# espnative-deadrail-2-2.net
KiCad netlist of a schematic drawn in EAGLE
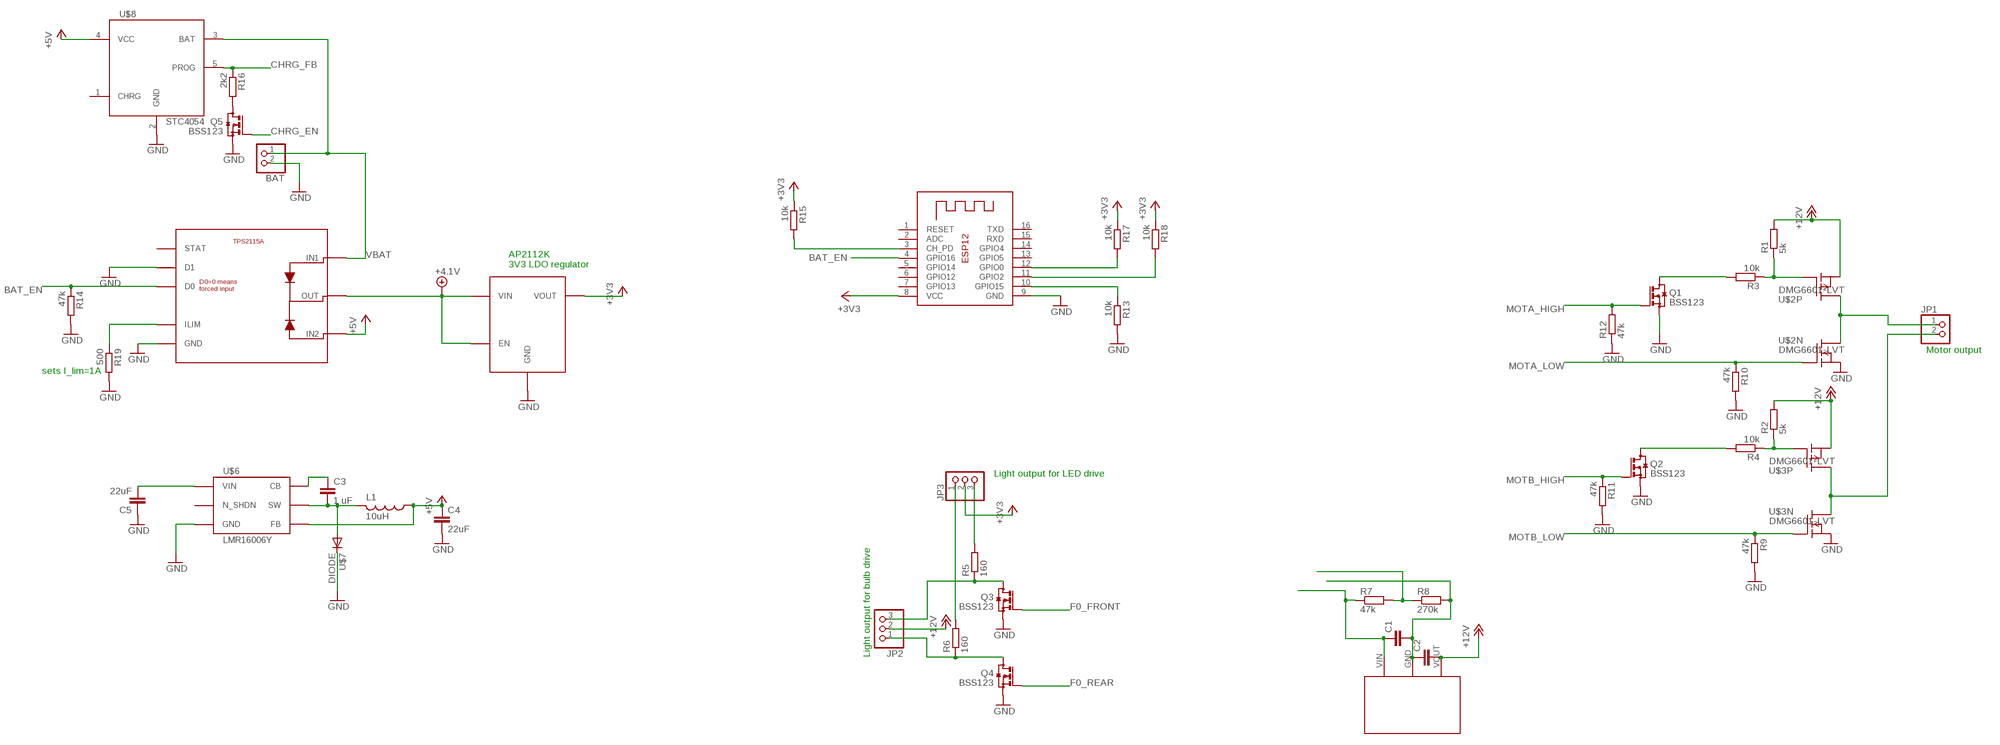
[diagram p0: schematic, sheet 1]

(export (version "E")
  (design (tool "Eeschema 10.0.6"))
  (components
    (comp (ref "BAT")
      (value "JST_2PIN-SMT-RA")
      (footprint "eagle-import:JST-PH-2-SMT-RA")
      (libsource (lib "eagle-import") (part "JST_2PIN-SMT-RA"))
    )
    (comp (ref "C1")
      (value "C-EUC1210")
      (footprint "eagle-import:C1210")
      (libsource (lib "eagle-import") (part "C-EUC1210"))
    )
    (comp (ref "C2")
      (value "C-EUC1210")
      (footprint "eagle-import:C1210")
      (libsource (lib "eagle-import") (part "C-EUC1210"))
    )
    (comp (ref "C3")
      (value "1 uF")
      (footprint "eagle-import:C0603")
      (libsource (lib "eagle-import") (part "C-EUC0603"))
    )
    (comp (ref "C4")
      (value "22uF")
      (footprint "eagle-import:C0603")
      (libsource (lib "eagle-import") (part "C-EUC0603"))
    )
    (comp (ref "C5")
      (value "22uF")
      (footprint "eagle-import:C1206")
      (libsource (lib "eagle-import") (part "C-EUC1206"))
    )
    (comp (ref "JP1")
      (value "PINHD-1X2")
      (footprint "eagle-import:1X02")
      (libsource (lib "eagle-import") (part "PINHD-1X2"))
    )
    (comp (ref "JP2")
      (value "PINHD-1X3")
      (footprint "eagle-import:1X03")
      (libsource (lib "eagle-import") (part "PINHD-1X3"))
    )
    (comp (ref "JP3")
      (value "PINHD-1X3")
      (footprint "eagle-import:1X03")
      (libsource (lib "eagle-import") (part "PINHD-1X3"))
    )
    (comp (ref "L1")
      (value "10uH")
      (footprint "eagle-import:FDSD0420")
      (libsource (lib "eagle-import") (part "FDSD0420"))
    )
    (comp (ref "Q1")
      (value "BSS123")
      (footprint "eagle-import:SOT23")
      (libsource (lib "eagle-import") (part "BSS123"))
    )
    (comp (ref "Q2")
      (value "BSS123")
      (footprint "eagle-import:SOT23")
      (libsource (lib "eagle-import") (part "BSS123"))
    )
    (comp (ref "Q3")
      (value "BSS123")
      (footprint "eagle-import:SOT23")
      (libsource (lib "eagle-import") (part "BSS123"))
    )
    (comp (ref "Q4")
      (value "BSS123")
      (footprint "eagle-import:SOT23")
      (libsource (lib "eagle-import") (part "BSS123"))
    )
    (comp (ref "Q5")
      (value "BSS123")
      (footprint "eagle-import:SOT23")
      (libsource (lib "eagle-import") (part "BSS123"))
    )
    (comp (ref "R1")
      (value "5k")
      (footprint "eagle-import:R0805")
      (libsource (lib "eagle-import") (part "R-EU_R0805"))
    )
    (comp (ref "R2")
      (value "5k")
      (footprint "eagle-import:R0805")
      (libsource (lib "eagle-import") (part "R-EU_R0805"))
    )
    (comp (ref "R3")
      (value "10k")
      (footprint "eagle-import:R0805")
      (libsource (lib "eagle-import") (part "R-EU_R0805"))
    )
    (comp (ref "R4")
      (value "10k")
      (footprint "eagle-import:R0805")
      (libsource (lib "eagle-import") (part "R-EU_R0805"))
    )
    (comp (ref "R5")
      (value "160")
      (footprint "eagle-import:R0805")
      (libsource (lib "eagle-import") (part "R-EU_R0805"))
    )
    (comp (ref "R6")
      (value "160")
      (footprint "eagle-import:R0805")
      (libsource (lib "eagle-import") (part "R-EU_R0805"))
    )
    (comp (ref "R7")
      (value "47k")
      (footprint "eagle-import:R0805")
      (libsource (lib "eagle-import") (part "R-EU_R0805"))
    )
    (comp (ref "R8")
      (value "270k")
      (footprint "eagle-import:R0805")
      (libsource (lib "eagle-import") (part "R-EU_R0805"))
    )
    (comp (ref "R9")
      (value "47k")
      (footprint "eagle-import:R0805")
      (libsource (lib "eagle-import") (part "R-EU_R0805"))
    )
    (comp (ref "R10")
      (value "47k")
      (footprint "eagle-import:R0805")
      (libsource (lib "eagle-import") (part "R-EU_R0805"))
    )
    (comp (ref "R11")
      (value "47k")
      (footprint "eagle-import:R0805")
      (libsource (lib "eagle-import") (part "R-EU_R0805"))
    )
    (comp (ref "R12")
      (value "47k")
      (footprint "eagle-import:R0805")
      (libsource (lib "eagle-import") (part "R-EU_R0805"))
    )
    (comp (ref "R13")
      (value "10k")
      (footprint "eagle-import:R0603")
      (libsource (lib "eagle-import") (part "R-EU_R0603"))
    )
    (comp (ref "R14")
      (value "47k")
      (footprint "eagle-import:R0603")
      (libsource (lib "eagle-import") (part "R-EU_R0603"))
    )
    (comp (ref "R15")
      (value "10k")
      (footprint "eagle-import:R0603")
      (libsource (lib "eagle-import") (part "R-EU_R0603"))
    )
    (comp (ref "R16")
      (value "2k2")
      (footprint "eagle-import:R0603")
      (libsource (lib "eagle-import") (part "R-EU_R0603"))
    )
    (comp (ref "R17")
      (value "10k")
      (footprint "eagle-import:R0603")
      (libsource (lib "eagle-import") (part "R-EU_R0603"))
    )
    (comp (ref "R18")
      (value "10k")
      (footprint "eagle-import:R0603")
      (libsource (lib "eagle-import") (part "R-EU_R0603"))
    )
    (comp (ref "R19")
      (value "500")
      (footprint "eagle-import:R0603")
      (libsource (lib "eagle-import") (part "R-EU_R0603"))
    )
    (comp (ref "U$1")
      (value "AP2112K-3V3")
      (footprint "eagle-import:SOT23-5L")
      (libsource (lib "eagle-import") (part "AP2112K"))
    )
    (comp (ref "U$2")
      (value "DMG6601-LVT")
      (footprint "eagle-import:TSOT-26")
      (libsource (lib "eagle-import") (part "DMG6601-LVT"))
    )
    (comp (ref "U$3")
      (value "DMG6601-LVT")
      (footprint "eagle-import:TSOT-26")
      (libsource (lib "eagle-import") (part "DMG6601-LVT"))
    )
    (comp (ref "U$4")
      (value "TPS2115A")
      (footprint "eagle-import:TSSOP-8")
      (libsource (lib "eagle-import") (part "TPS2115A"))
    )
    (comp (ref "U$5")
      (value "POLOLU-VREG12")
      (footprint "eagle-import:POLOLU-REGULATOR")
      (libsource (lib "eagle-import") (part "POLOLU-VREG12"))
    )
    (comp (ref "U$6")
      (value "LMR16006Y")
      (footprint "eagle-import:SOT23-6")
      (libsource (lib "eagle-import") (part "LMR16006Y"))
    )
    (comp (ref "U$7")
      (value "DIODE")
      (footprint "eagle-import:DIODE-1206")
      (libsource (lib "eagle-import") (part "DIODE"))
    )
    (comp (ref "U$8")
      (value "STC4054")
      (footprint "eagle-import:SOT23-5L")
      (libsource (lib "eagle-import") (part "STC4054"))
    )
    (comp (ref "X1")
      (value "ESP-12")
      (footprint "eagle-import:ESP-12")
      (libsource (lib "eagle-import") (part "ESP-12"))
    )
  )
  (nets
    (net (code "1") (name "+3V3") (class "Default")
      (node (ref "JP3") (pin "2") (pinfunction "2_2") (pintype "passive"))
      (node (ref "R15") (pin "1") (pinfunction "1_1") (pintype "passive"))
      (node (ref "R17") (pin "1") (pinfunction "1_1") (pintype "passive"))
      (node (ref "R18") (pin "1") (pinfunction "1_1") (pintype "passive"))
      (node (ref "U$1") (pin "5") (pinfunction "VOUT_5") (pintype "bidirectional"))
      (node (ref "X1") (pin "8") (pinfunction "VCC_8") (pintype "power_in"))
    )
    (net (code "2") (name "+4.1V") (class "Default")
      (node (ref "U$1") (pin "1") (pinfunction "VIN_1") (pintype "bidirectional"))
      (node (ref "U$1") (pin "3") (pinfunction "EN_3") (pintype "bidirectional"))
      (node (ref "U$4") (pin "7") (pinfunction "OUT_7") (pintype "bidirectional"))
    )
    (net (code "3") (name "+5V") (class "Default")
      (node (ref "C4") (pin "1") (pinfunction "1_1") (pintype "passive"))
      (node (ref "L1") (pin "P$1") (pinfunction "1_P$1") (pintype "passive"))
      (node (ref "U$4") (pin "6") (pinfunction "IN2_6") (pintype "bidirectional"))
      (node (ref "U$6") (pin "3") (pinfunction "FB_3") (pintype "bidirectional"))
      (node (ref "U$8") (pin "4") (pinfunction "VCC_4") (pintype "bidirectional"))
    )
    (net (code "4") (name "+12V") (class "Default")
      (node (ref "C2") (pin "2") (pinfunction "2_2") (pintype "passive"))
      (node (ref "JP2") (pin "2") (pinfunction "2_2") (pintype "passive"))
      (node (ref "R1") (pin "2") (pinfunction "2_2") (pintype "passive"))
      (node (ref "R2") (pin "2") (pinfunction "2_2") (pintype "passive"))
      (node (ref "U$2") (pin "2") (pinfunction "S_2") (pintype "passive"))
      (node (ref "U$3") (pin "2") (pinfunction "S_2") (pintype "passive"))
      (node (ref "U$5") (pin "VOUT") (pinfunction "VOUT_VOUT") (pintype "bidirectional"))
    )
    (net (code "5") (name "/BAT_EN") (class "Default")
      (node (ref "R14") (pin "1") (pinfunction "1_1") (pintype "passive"))
      (node (ref "U$4") (pin "2") (pinfunction "D0_2") (pintype "bidirectional"))
      (node (ref "X1") (pin "4") (pinfunction "GPIO16_4") (pintype "bidirectional"))
    )
    (net (code "6") (name "/CHRG_EN") (class "Default")
      (node (ref "Q5") (pin "1") (pinfunction "G_1") (pintype "passive"))
    )
    (net (code "7") (name "/CHRG_FB") (class "Default")
      (node (ref "R16") (pin "1") (pinfunction "1_1") (pintype "passive"))
      (node (ref "U$8") (pin "5") (pinfunction "PROG_5") (pintype "bidirectional"))
    )
    (net (code "8") (name "/F0_FRONT") (class "Default")
      (node (ref "Q3") (pin "1") (pinfunction "G_1") (pintype "passive"))
    )
    (net (code "9") (name "/F0_REAR") (class "Default")
      (node (ref "Q4") (pin "1") (pinfunction "G_1") (pintype "passive"))
    )
    (net (code "10") (name "/MOTA_HIGH") (class "Default")
      (node (ref "Q1") (pin "1") (pinfunction "G_1") (pintype "passive"))
      (node (ref "R12") (pin "2") (pinfunction "2_2") (pintype "passive"))
    )
    (net (code "11") (name "/MOTA_LOW") (class "Default")
      (node (ref "R10") (pin "1") (pinfunction "1_1") (pintype "passive"))
      (node (ref "U$2") (pin "1") (pinfunction "G_1") (pintype "passive"))
    )
    (net (code "12") (name "/MOTB_HIGH") (class "Default")
      (node (ref "Q2") (pin "1") (pinfunction "G_1") (pintype "passive"))
      (node (ref "R11") (pin "1") (pinfunction "1_1") (pintype "passive"))
    )
    (net (code "13") (name "/MOTB_LOW") (class "Default")
      (node (ref "R9") (pin "1") (pinfunction "1_1") (pintype "passive"))
      (node (ref "U$3") (pin "1") (pinfunction "G_1") (pintype "passive"))
    )
    (net (code "14") (name "/VBAT") (class "Default")
      (node (ref "BAT") (pin "1") (pinfunction "2_1") (pintype "passive"))
      (node (ref "C1") (pin "1") (pinfunction "1_1") (pintype "passive"))
      (node (ref "R7") (pin "1") (pinfunction "1_1") (pintype "passive"))
      (node (ref "U$4") (pin "8") (pinfunction "IN1_8") (pintype "bidirectional"))
      (node (ref "U$5") (pin "VIN") (pinfunction "VIN_VIN") (pintype "bidirectional"))
      (node (ref "U$8") (pin "3") (pinfunction "BAT_3") (pintype "bidirectional"))
    )
    (net (code "15") (name "GND") (class "Default")
      (node (ref "BAT") (pin "2") (pinfunction "1_2") (pintype "passive"))
      (node (ref "C1") (pin "2") (pinfunction "2_2") (pintype "passive"))
      (node (ref "C2") (pin "1") (pinfunction "1_1") (pintype "passive"))
      (node (ref "C4") (pin "2") (pinfunction "2_2") (pintype "passive"))
      (node (ref "C5") (pin "1") (pinfunction "1_1") (pintype "passive"))
      (node (ref "Q1") (pin "2") (pinfunction "S_2") (pintype "passive"))
      (node (ref "Q2") (pin "2") (pinfunction "S_2") (pintype "passive"))
      (node (ref "Q3") (pin "2") (pinfunction "S_2") (pintype "passive"))
      (node (ref "Q4") (pin "2") (pinfunction "S_2") (pintype "passive"))
      (node (ref "Q5") (pin "2") (pinfunction "S_2") (pintype "passive"))
      (node (ref "R10") (pin "2") (pinfunction "2_2") (pintype "passive"))
      (node (ref "R11") (pin "2") (pinfunction "2_2") (pintype "passive"))
      (node (ref "R12") (pin "1") (pinfunction "1_1") (pintype "passive"))
      (node (ref "R13") (pin "2") (pinfunction "2_2") (pintype "passive"))
      (node (ref "R14") (pin "2") (pinfunction "2_2") (pintype "passive"))
      (node (ref "R19") (pin "2") (pinfunction "2_2") (pintype "passive"))
      (node (ref "R8") (pin "2") (pinfunction "2_2") (pintype "passive"))
      (node (ref "R9") (pin "2") (pinfunction "2_2") (pintype "passive"))
      (node (ref "U$1") (pin "2") (pinfunction "GND_2") (pintype "bidirectional"))
      (node (ref "U$2") (pin "5") (pinfunction "S_5") (pintype "passive"))
      (node (ref "U$3") (pin "5") (pinfunction "S_5") (pintype "passive"))
      (node (ref "U$4") (pin "3") (pinfunction "D1_3") (pintype "bidirectional"))
      (node (ref "U$4") (pin "5") (pinfunction "GND_5") (pintype "bidirectional"))
      (node (ref "U$5") (pin "GND") (pinfunction "GND_GND") (pintype "bidirectional"))
      (node (ref "U$6") (pin "2") (pinfunction "GND_2") (pintype "bidirectional"))
      (node (ref "U$7") (pin "C") (pinfunction "C_C") (pintype "passive"))
      (node (ref "U$8") (pin "2") (pinfunction "GND_2") (pintype "bidirectional"))
      (node (ref "X1") (pin "9") (pinfunction "GND_9") (pintype "power_in"))
    )
    (net (code "16") (name "Net-(JP3-Pad1)") (class "Default")
      (node (ref "JP3") (pin "1") (pinfunction "1_1") (pintype "passive"))
      (node (ref "R6") (pin "2") (pinfunction "2_2") (pintype "passive"))
    )
    (net (code "17") (name "Net-(JP3-Pad3)") (class "Default")
      (node (ref "JP3") (pin "3") (pinfunction "3_3") (pintype "passive"))
      (node (ref "R5") (pin "2") (pinfunction "2_2") (pintype "passive"))
    )
    (net (code "18") (name "Net-(L1-2)") (class "Default")
      (node (ref "C3") (pin "2") (pinfunction "2_2") (pintype "passive"))
      (node (ref "L1") (pin "P$2") (pinfunction "2_P$2") (pintype "passive"))
      (node (ref "U$6") (pin "6") (pinfunction "SW_6") (pintype "bidirectional"))
      (node (ref "U$7") (pin "A") (pinfunction "A_A") (pintype "passive"))
    )
    (net (code "19") (name "Net-(Q1-D)") (class "Default")
      (node (ref "Q1") (pin "3") (pinfunction "D_3") (pintype "passive"))
      (node (ref "R3") (pin "2") (pinfunction "2_2") (pintype "passive"))
    )
    (net (code "20") (name "Net-(Q2-D)") (class "Default")
      (node (ref "Q2") (pin "3") (pinfunction "D_3") (pintype "passive"))
      (node (ref "R4") (pin "2") (pinfunction "2_2") (pintype "passive"))
    )
    (net (code "21") (name "Net-(Q3-D)") (class "Default")
      (node (ref "JP2") (pin "3") (pinfunction "3_3") (pintype "passive"))
      (node (ref "Q3") (pin "3") (pinfunction "D_3") (pintype "passive"))
      (node (ref "R5") (pin "1") (pinfunction "1_1") (pintype "passive"))
    )
    (net (code "22") (name "Net-(Q4-D)") (class "Default")
      (node (ref "JP2") (pin "1") (pinfunction "1_1") (pintype "passive"))
      (node (ref "Q4") (pin "3") (pinfunction "D_3") (pintype "passive"))
      (node (ref "R6") (pin "1") (pinfunction "1_1") (pintype "passive"))
    )
    (net (code "23") (name "Net-(Q5-D)") (class "Default")
      (node (ref "Q5") (pin "3") (pinfunction "D_3") (pintype "passive"))
      (node (ref "R16") (pin "2") (pinfunction "2_2") (pintype "passive"))
    )
    (net (code "24") (name "Net-(R7-Pad2)") (class "Default")
      (node (ref "R7") (pin "2") (pinfunction "2_2") (pintype "passive"))
      (node (ref "R8") (pin "1") (pinfunction "1_1") (pintype "passive"))
    )
    (net (code "25") (name "Net-(U$2A-D)") (class "Default")
      (node (ref "JP1") (pin "1") (pinfunction "1_1") (pintype "passive"))
      (node (ref "U$2") (pin "4") (pinfunction "D_4") (pintype "passive"))
      (node (ref "U$2") (pin "6") (pinfunction "D_6") (pintype "passive"))
    )
    (net (code "26") (name "Net-(U$2B-G)") (class "Default")
      (node (ref "R1") (pin "1") (pinfunction "1_1") (pintype "passive"))
      (node (ref "R3") (pin "1") (pinfunction "1_1") (pintype "passive"))
      (node (ref "U$2") (pin "3") (pinfunction "G_3") (pintype "passive"))
    )
    (net (code "27") (name "Net-(U$3A-D)") (class "Default")
      (node (ref "JP1") (pin "2") (pinfunction "2_2") (pintype "passive"))
      (node (ref "U$3") (pin "4") (pinfunction "D_4") (pintype "passive"))
      (node (ref "U$3") (pin "6") (pinfunction "D_6") (pintype "passive"))
    )
    (net (code "28") (name "Net-(U$3B-G)") (class "Default")
      (node (ref "R2") (pin "1") (pinfunction "1_1") (pintype "passive"))
      (node (ref "R4") (pin "1") (pinfunction "1_1") (pintype "passive"))
      (node (ref "U$3") (pin "3") (pinfunction "G_3") (pintype "passive"))
    )
    (net (code "29") (name "Net-(U$4-ILIM)") (class "Default")
      (node (ref "R19") (pin "1") (pinfunction "1_1") (pintype "passive"))
      (node (ref "U$4") (pin "4") (pinfunction "ILIM_4") (pintype "bidirectional"))
    )
    (net (code "30") (name "Net-(U$6-CB)") (class "Default")
      (node (ref "C3") (pin "1") (pinfunction "1_1") (pintype "passive"))
      (node (ref "U$6") (pin "1") (pinfunction "CB_1") (pintype "bidirectional"))
    )
    (net (code "31") (name "Net-(U$6-VIN)") (class "Default")
      (node (ref "C5") (pin "2") (pinfunction "2_2") (pintype "passive"))
      (node (ref "U$6") (pin "5") (pinfunction "VIN_5") (pintype "bidirectional"))
    )
    (net (code "32") (name "Net-(X1-CH_PD)") (class "Default")
      (node (ref "R15") (pin "2") (pinfunction "2_2") (pintype "passive"))
      (node (ref "X1") (pin "3") (pinfunction "CH_PD_3") (pintype "input"))
    )
    (net (code "33") (name "Net-(X1-GPIO0)") (class "Default")
      (node (ref "R17") (pin "2") (pinfunction "2_2") (pintype "passive"))
      (node (ref "X1") (pin "12") (pinfunction "GPIO0_12") (pintype "bidirectional"))
    )
    (net (code "34") (name "Net-(X1-GPIO2)") (class "Default")
      (node (ref "R18") (pin "2") (pinfunction "2_2") (pintype "passive"))
      (node (ref "X1") (pin "11") (pinfunction "GPIO2_11") (pintype "bidirectional"))
    )
    (net (code "35") (name "Net-(X1-GPIO15)") (class "Default")
      (node (ref "R13") (pin "1") (pinfunction "1_1") (pintype "passive"))
      (node (ref "X1") (pin "10") (pinfunction "GPIO15_10") (pintype "bidirectional"))
    )
    (net (code "36") (name "unconnected-(U$4-STAT-Pad1)") (class "Default")
      (node (ref "U$4") (pin "1") (pinfunction "STAT_1") (pintype "bidirectional"))
    )
    (net (code "37") (name "unconnected-(U$6-N_SHDN-Pad4)") (class "Default")
      (node (ref "U$6") (pin "4") (pinfunction "N_SHDN_4") (pintype "bidirectional"))
    )
    (net (code "38") (name "unconnected-(U$8-CHRG-Pad1)") (class "Default")
      (node (ref "U$8") (pin "1") (pinfunction "CHRG_1") (pintype "bidirectional"))
    )
    (net (code "39") (name "unconnected-(X1-ADC-Pad2)") (class "Default")
      (node (ref "X1") (pin "2") (pinfunction "ADC_2") (pintype "passive"))
    )
    (net (code "40") (name "unconnected-(X1-GPIO4-Pad14)") (class "Default")
      (node (ref "X1") (pin "14") (pinfunction "GPIO4_14") (pintype "bidirectional"))
    )
    (net (code "41") (name "unconnected-(X1-GPIO5-Pad13)") (class "Default")
      (node (ref "X1") (pin "13") (pinfunction "GPIO5_13") (pintype "bidirectional"))
    )
    (net (code "42") (name "unconnected-(X1-GPIO12-Pad6)") (class "Default")
      (node (ref "X1") (pin "6") (pinfunction "GPIO12_6") (pintype "bidirectional"))
    )
    (net (code "43") (name "unconnected-(X1-GPIO13-Pad7)") (class "Default")
      (node (ref "X1") (pin "7") (pinfunction "GPIO13_7") (pintype "bidirectional"))
    )
    (net (code "44") (name "unconnected-(X1-GPIO14-Pad5)") (class "Default")
      (node (ref "X1") (pin "5") (pinfunction "GPIO14_5") (pintype "bidirectional"))
    )
    (net (code "45") (name "unconnected-(X1-RESET-Pad1)") (class "Default")
      (node (ref "X1") (pin "1") (pinfunction "RESET_1") (pintype "input"))
    )
    (net (code "46") (name "unconnected-(X1-RXD-Pad15)") (class "Default")
      (node (ref "X1") (pin "15") (pinfunction "RXD_15") (pintype "input"))
    )
    (net (code "47") (name "unconnected-(X1-TXD-Pad16)") (class "Default")
      (node (ref "X1") (pin "16") (pinfunction "TXD_16") (pintype "output"))
    )
  )
)
